# CarrinhoAcel.net
KiCad netlist of a schematic drawn in EAGLE
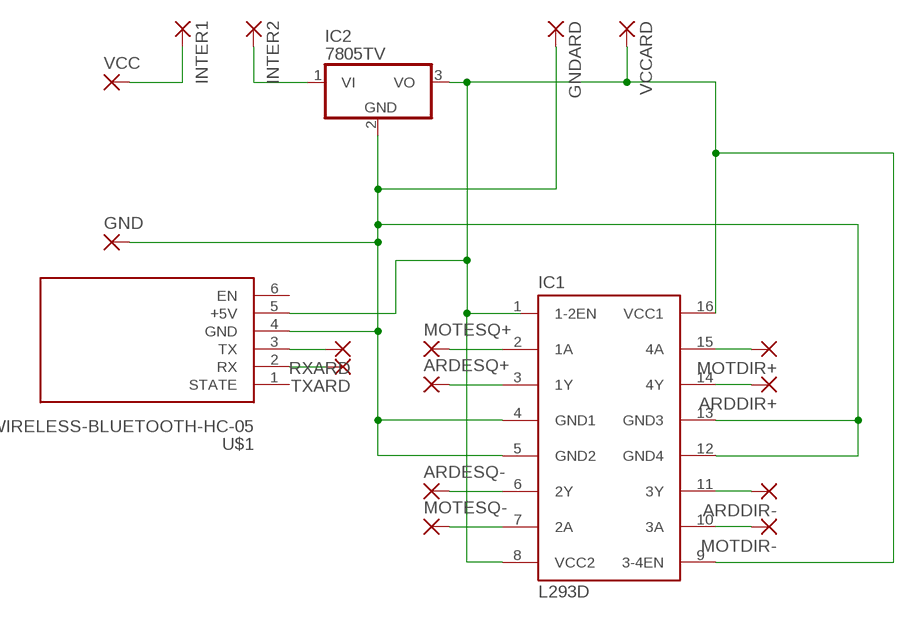
[diagram p0: schematic, sheet 1]

(export (version "E")
  (design (tool "Eeschema 10.0.6"))
  (components
    (comp (ref "ARDDIR+")
      (value "2,15/1,0")
      (footprint "eagle-import:2,15_1,0")
      (libsource (lib "eagle-import") (part "2,15/1,0"))
    )
    (comp (ref "ARDDIR-")
      (value "2,15/1,0")
      (footprint "eagle-import:2,15_1,0")
      (libsource (lib "eagle-import") (part "2,15/1,0"))
    )
    (comp (ref "ARDESQ+")
      (value "2,15/1,0")
      (footprint "eagle-import:2,15_1,0")
      (libsource (lib "eagle-import") (part "2,15/1,0"))
    )
    (comp (ref "ARDESQ-")
      (value "2,15/1,0")
      (footprint "eagle-import:2,15_1,0")
      (libsource (lib "eagle-import") (part "2,15/1,0"))
    )
    (comp (ref "GND")
      (value "2,15/1,0")
      (footprint "eagle-import:2,15_1,0")
      (libsource (lib "eagle-import") (part "2,15/1,0"))
    )
    (comp (ref "GNDARD")
      (value "2,15/1,0")
      (footprint "eagle-import:2,15_1,0")
      (libsource (lib "eagle-import") (part "2,15/1,0"))
    )
    (comp (ref "IC1")
      (value "L293D")
      (footprint "eagle-import:DIL16")
      (libsource (lib "eagle-import") (part "L293D"))
    )
    (comp (ref "IC2")
      (value "7805TV")
      (footprint "eagle-import:TO220V")
      (libsource (lib "eagle-import") (part "78TV05"))
    )
    (comp (ref "INTER1")
      (value "2,15/1,0")
      (footprint "eagle-import:2,15_1,0")
      (libsource (lib "eagle-import") (part "2,15/1,0"))
    )
    (comp (ref "INTER2")
      (value "2,15/1,0")
      (footprint "eagle-import:2,15_1,0")
      (libsource (lib "eagle-import") (part "2,15/1,0"))
    )
    (comp (ref "MOTDIR+")
      (value "2,15/1,0")
      (footprint "eagle-import:2,15_1,0")
      (libsource (lib "eagle-import") (part "2,15/1,0"))
    )
    (comp (ref "MOTDIR-")
      (value "2,15/1,0")
      (footprint "eagle-import:2,15_1,0")
      (libsource (lib "eagle-import") (part "2,15/1,0"))
    )
    (comp (ref "MOTESQ+")
      (value "2,15/1,0")
      (footprint "eagle-import:2,15_1,0")
      (libsource (lib "eagle-import") (part "2,15/1,0"))
    )
    (comp (ref "MOTESQ-")
      (value "2,15/1,0")
      (footprint "eagle-import:2,15_1,0")
      (libsource (lib "eagle-import") (part "2,15/1,0"))
    )
    (comp (ref "RXARD")
      (value "2,15/1,0")
      (footprint "eagle-import:2,15_1,0")
      (libsource (lib "eagle-import") (part "2,15/1,0"))
    )
    (comp (ref "TXARD")
      (value "2,15/1,0")
      (footprint "eagle-import:2,15_1,0")
      (libsource (lib "eagle-import") (part "2,15/1,0"))
    )
    (comp (ref "U$1")
      (value "WIRELESS-BLUETOOTH-HC-05")
      (footprint "eagle-import:WIRELESS-BLUETOOTH-HC-05")
      (libsource (lib "eagle-import") (part "WIRELESS-BLUETOOTH-HC-05"))
    )
    (comp (ref "VCC")
      (value "2,15/1,0")
      (footprint "eagle-import:2,15_1,0")
      (libsource (lib "eagle-import") (part "2,15/1,0"))
    )
    (comp (ref "VCCARD")
      (value "2,15/1,0")
      (footprint "eagle-import:2,15_1,0")
      (libsource (lib "eagle-import") (part "2,15/1,0"))
    )
  )
  (nets
    (net (code "1") (name "Net-(ARDDIR+-P)") (class "Default")
      (node (ref "ARDDIR+") (pin "1") (pinfunction "P_1") (pintype "passive"))
      (node (ref "IC1") (pin "14") (pinfunction "4Y_14") (pintype "output"))
    )
    (net (code "2") (name "Net-(ARDDIR--P)") (class "Default")
      (node (ref "ARDDIR-") (pin "1") (pinfunction "P_1") (pintype "passive"))
      (node (ref "IC1") (pin "11") (pinfunction "3Y_11") (pintype "output"))
    )
    (net (code "3") (name "Net-(ARDESQ+-P)") (class "Default")
      (node (ref "ARDESQ+") (pin "1") (pinfunction "P_1") (pintype "passive"))
      (node (ref "IC1") (pin "3") (pinfunction "1Y_3") (pintype "output"))
    )
    (net (code "4") (name "Net-(ARDESQ--P)") (class "Default")
      (node (ref "ARDESQ-") (pin "1") (pinfunction "P_1") (pintype "passive"))
      (node (ref "IC1") (pin "6") (pinfunction "2Y_6") (pintype "output"))
    )
    (net (code "5") (name "Net-(GND-P)") (class "Default")
      (node (ref "GND") (pin "1") (pinfunction "P_1") (pintype "passive"))
      (node (ref "GNDARD") (pin "1") (pinfunction "P_1") (pintype "passive"))
      (node (ref "IC1") (pin "12") (pinfunction "GND4_12") (pintype "power_in"))
      (node (ref "IC1") (pin "13") (pinfunction "GND3_13") (pintype "power_in"))
      (node (ref "IC1") (pin "4") (pinfunction "GND1_4") (pintype "power_in"))
      (node (ref "IC1") (pin "5") (pinfunction "GND2_5") (pintype "power_in"))
      (node (ref "IC2") (pin "2") (pinfunction "GND_2") (pintype "passive"))
      (node (ref "U$1") (pin "4") (pinfunction "GND_4") (pintype "power_in"))
    )
    (net (code "6") (name "Net-(IC1-1-2EN)") (class "Default")
      (node (ref "IC1") (pin "1") (pinfunction "1-2EN_1") (pintype "input"))
      (node (ref "IC1") (pin "16") (pinfunction "VCC1_16") (pintype "power_in"))
      (node (ref "IC1") (pin "8") (pinfunction "VCC2_8") (pintype "power_in"))
      (node (ref "IC1") (pin "9") (pinfunction "3-4EN_9") (pintype "input"))
      (node (ref "IC2") (pin "3") (pinfunction "VO_3") (pintype "passive"))
      (node (ref "U$1") (pin "5") (pinfunction "+5V_5") (pintype "power_in"))
      (node (ref "VCCARD") (pin "1") (pinfunction "P_1") (pintype "passive"))
    )
    (net (code "7") (name "Net-(IC1-1A)") (class "Default")
      (node (ref "IC1") (pin "2") (pinfunction "1A_2") (pintype "input"))
      (node (ref "MOTESQ+") (pin "1") (pinfunction "P_1") (pintype "passive"))
    )
    (net (code "8") (name "Net-(IC1-2A)") (class "Default")
      (node (ref "IC1") (pin "7") (pinfunction "2A_7") (pintype "input"))
      (node (ref "MOTESQ-") (pin "1") (pinfunction "P_1") (pintype "passive"))
    )
    (net (code "9") (name "Net-(IC1-3A)") (class "Default")
      (node (ref "IC1") (pin "10") (pinfunction "3A_10") (pintype "input"))
      (node (ref "MOTDIR-") (pin "1") (pinfunction "P_1") (pintype "passive"))
    )
    (net (code "10") (name "Net-(IC1-4A)") (class "Default")
      (node (ref "IC1") (pin "15") (pinfunction "4A_15") (pintype "input"))
      (node (ref "MOTDIR+") (pin "1") (pinfunction "P_1") (pintype "passive"))
    )
    (net (code "11") (name "Net-(IC2-VI)") (class "Default")
      (node (ref "IC2") (pin "1") (pinfunction "VI_1") (pintype "input"))
      (node (ref "INTER2") (pin "1") (pinfunction "P_1") (pintype "passive"))
    )
    (net (code "12") (name "Net-(INTER1-P)") (class "Default")
      (node (ref "INTER1") (pin "1") (pinfunction "P_1") (pintype "passive"))
      (node (ref "VCC") (pin "1") (pinfunction "P_1") (pintype "passive"))
    )
    (net (code "13") (name "Net-(RXARD-P)") (class "Default")
      (node (ref "RXARD") (pin "1") (pinfunction "P_1") (pintype "passive"))
      (node (ref "U$1") (pin "3") (pinfunction "TX_3") (pintype "bidirectional"))
    )
    (net (code "14") (name "Net-(TXARD-P)") (class "Default")
      (node (ref "TXARD") (pin "1") (pinfunction "P_1") (pintype "passive"))
      (node (ref "U$1") (pin "2") (pinfunction "RX_2") (pintype "bidirectional"))
    )
    (net (code "15") (name "unconnected-(U$1-EN-Pad6)") (class "Default")
      (node (ref "U$1") (pin "6") (pinfunction "EN_6") (pintype "bidirectional"))
    )
    (net (code "16") (name "unconnected-(U$1-STATE-Pad1)") (class "Default")
      (node (ref "U$1") (pin "1") (pinfunction "STATE_1") (pintype "bidirectional"))
    )
  )
)
